# Booster_USER_IFC.net
KiCad netlist of a schematic drawn in Altium Designer
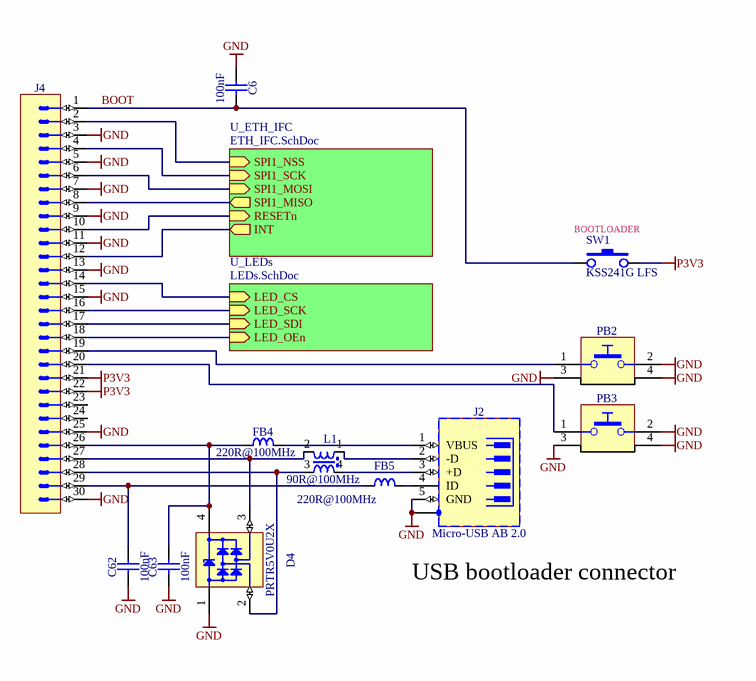
[diagram p0: Booster_USER_IFC.SchDoc]

(export (version "E")
  (design (tool "Eeschema 10.0.6"))
  (components
    (comp (ref "C6")
      (value "100nF")
      (footprint "CAPC1005X55N")
      (description "Non-polarised capacitor")
      (fields
        (field (name "PART NUMBER") "CC0402_100NF_16V_10%_X7R")
        (field (name "VOLTAGE") "16V")
        (field (name "AUTHOR") "CERN DEM JLC")
      )
      (libsource (lib "Capacitors") (part "Capacitor - non polarized"))
    )
    (comp (ref "C62")
      (value "100nF")
      (footprint "CAPC1005X55N")
      (description "Non-polarised capacitor")
      (fields
        (field (name "PART NUMBER") "CC0402_100NF_16V_10%_X7R")
        (field (name "VOLTAGE") "16V")
        (field (name "AUTHOR") "CERN DEM JLC")
      )
      (libsource (lib "Capacitors") (part "Capacitor - non polarized"))
    )
    (comp (ref "C63")
      (value "100nF")
      (footprint "CAPC1005X55N")
      (description "Non-polarised capacitor")
      (fields
        (field (name "PART NUMBER") "CC0402_100NF_16V_10%_X7R")
        (field (name "VOLTAGE") "16V")
        (field (name "AUTHOR") "CERN DEM JLC")
      )
      (libsource (lib "Capacitors") (part "Capacitor - non polarized"))
    )
    (comp (ref "D4")
      (value "PRTR5V0U2X")
      (footprint "SOT190P230X110-4N")
      (description "Ultra Low Capacitance Double Rail-to-Rail ESD Protection Diode")
      (fields
        (field (name "VOLTAGE") "5.5V")
        (field (name "MANUFACTURER") "NXP SEMICONDUCTORS")
        (field (name "AUTHOR") "CERN DEM JLC")
      )
      (libsource (lib "ICs And Semiconductors") (part "PRTR5V0U2X"))
    )
    (comp (ref "FB4")
      (value "220R@100MHz")
      (footprint "INDC2012X105N")
      (description "Inductor")
      (fields
        (field (name "PART NUMBER") "IND0805_MURATA_BLM21PG221SN1D")
        (field (name "POWER") "2A")
        (field (name "AUTHOR") "CERN DEM JLC")
      )
      (libsource (lib "Inductors & Transformers") (part "Inductor"))
    )
    (comp (ref "FB5")
      (value "220R@100MHz")
      (footprint "INDC2012X105N")
      (description "Inductor")
      (fields
        (field (name "PART NUMBER") "IND0805_MURATA_BLM21PG221SN1D")
        (field (name "POWER") "2A")
        (field (name "AUTHOR") "CERN DEM JLC")
      )
      (libsource (lib "Inductors & Transformers") (part "Inductor"))
    )
    (comp (ref "J2")
      (value "Micro-USB AB 2.0")
      (footprint "HIROSE_ZX62RD-AB-5P8")
      (description "5 Pin + 1 Shield USB Receptacle")
      (fields
        (field (name "PART NUMBER") "HIROSE_ZX62RD-AB-5P8")
        (field (name "MANUFACTURER") "HIROSE (HRS)")
        (field (name "AUTHOR") "CERN DEM JLC")
      )
      (libsource (lib "Connectors") (part "Connector USB 5 Pin + 1Shield"))
    )
    (comp (ref "J4")
      (value "~")
      (footprint "3M_N2530-6002RB")
      (description "Connector 30 Male")
      (fields
        (field (name "PART NUMBER") "3M_N2530-6002RB")
        (field (name "MANUFACTURER") "3M")
        (field (name "AUTHOR") "CERN DEM JLC")
      )
      (libsource (lib "Connectors") (part "Connector 30 Male"))
    )
    (comp (ref "L1")
      (value "90R@100MHz")
      (footprint "IND_MURATA_DLW21S")
      (description "Inductor Common Mode")
      (fields
        (field (name "PART NUMBER") "IND_MURATA_DLW21SN900SQ2L")
        (field (name "POWER") "330mA")
        (field (name "AUTHOR") "CERN DEM JLC")
      )
      (libsource (lib "Inductors & Transformers") (part "Inductor Common Mode 1Dot-2 4Dot-3"))
    )
    (comp (ref "PB2")
      (value "Push Button")
      (footprint "PB_TYCO_1-1825027-1")
      (description "Push-Button Switch SPDT")
      (fields
        (field (name "PART NUMBER") "PB_TYCO_1-1825027-1")
        (field (name "MANUFACTURER") "TYCO ELECTRONICS")
        (field (name "AUTHOR") "CERN DEM JLC")
      )
      (libsource (lib "Eletro-mechanical") (part "PB SPST 1NO-2NO 34CASE"))
    )
    (comp (ref "PB3")
      (value "Push Button")
      (footprint "PB_TYCO_1-1825027-1")
      (description "Push-Button Switch SPDT")
      (fields
        (field (name "PART NUMBER") "PB_TYCO_1-1825027-1")
        (field (name "MANUFACTURER") "TYCO ELECTRONICS")
        (field (name "AUTHOR") "CERN DEM JLC")
      )
      (libsource (lib "Eletro-mechanical") (part "PB SPST 1NO-2NO 34CASE"))
    )
    (comp (ref "SW1")
      (value "KSS241G LFS")
      (footprint "KSS241G LFS")
      (description "Push button")
      (libsource (lib "LIBRARY_SCH") (part "SW-TACT_SMD_RA_mini"))
    )
  )
  (nets
    (net (code "1") (name "/BOOT") (class "Default")
      (node (ref "C6") (pin "2") (pinfunction "2_2") (pintype "passive"))
      (node (ref "J4") (pin "1") (pinfunction "1_1") (pintype "bidirectional"))
      (node (ref "SW1") (pin "1") (pinfunction "1_1") (pintype "passive"))
    )
    (net (code "2") (name "/INT") (class "Default")
      (node (ref "J4") (pin "12") (pinfunction "12_12") (pintype "bidirectional"))
    )
    (net (code "3") (name "/LED_CS") (class "Default")
      (node (ref "J4") (pin "14") (pinfunction "14_14") (pintype "bidirectional"))
    )
    (net (code "4") (name "/LED_OEn") (class "Default")
      (node (ref "J4") (pin "18") (pinfunction "18_18") (pintype "bidirectional"))
    )
    (net (code "5") (name "/LED_SCK") (class "Default")
      (node (ref "J4") (pin "16") (pinfunction "16_16") (pintype "bidirectional"))
    )
    (net (code "6") (name "/LED_SDI") (class "Default")
      (node (ref "J4") (pin "17") (pinfunction "17_17") (pintype "bidirectional"))
    )
    (net (code "7") (name "/RESETn") (class "Default")
      (node (ref "J4") (pin "10") (pinfunction "10_10") (pintype "bidirectional"))
    )
    (net (code "8") (name "/SPI1_MISO") (class "Default")
      (node (ref "J4") (pin "8") (pinfunction "8_8") (pintype "bidirectional"))
    )
    (net (code "9") (name "/SPI1_MOSI") (class "Default")
      (node (ref "J4") (pin "6") (pinfunction "6_6") (pintype "bidirectional"))
    )
    (net (code "10") (name "/SPI1_NSS") (class "Default")
      (node (ref "J4") (pin "2") (pinfunction "2_2") (pintype "bidirectional"))
    )
    (net (code "11") (name "/SPI1_SCK") (class "Default")
      (node (ref "J4") (pin "4") (pinfunction "4_4") (pintype "bidirectional"))
    )
    (net (code "12") (name "GND") (class "Default")
      (node (ref "C6") (pin "1") (pinfunction "1_1") (pintype "passive"))
      (node (ref "C62") (pin "1") (pinfunction "1_1") (pintype "passive"))
      (node (ref "C63") (pin "1") (pinfunction "1_1") (pintype "passive"))
      (node (ref "D4") (pin "1") (pinfunction "GND_1") (pintype "power_in"))
      (node (ref "J2") (pin "5") (pinfunction "GND_5") (pintype "bidirectional"))
      (node (ref "J2") (pin "6") (pinfunction "SH_6") (pintype "power_in"))
      (node (ref "J4") (pin "11") (pinfunction "11_11") (pintype "bidirectional"))
      (node (ref "J4") (pin "13") (pinfunction "13_13") (pintype "bidirectional"))
      (node (ref "J4") (pin "15") (pinfunction "15_15") (pintype "bidirectional"))
      (node (ref "J4") (pin "25") (pinfunction "25_25") (pintype "bidirectional"))
      (node (ref "J4") (pin "3") (pinfunction "3_3") (pintype "bidirectional"))
      (node (ref "J4") (pin "30") (pinfunction "30_30") (pintype "bidirectional"))
      (node (ref "J4") (pin "5") (pinfunction "5_5") (pintype "bidirectional"))
      (node (ref "J4") (pin "7") (pinfunction "7_7") (pintype "bidirectional"))
      (node (ref "J4") (pin "9") (pinfunction "9_9") (pintype "bidirectional"))
      (node (ref "PB2") (pin "2") (pinfunction "2_2") (pintype "passive"))
      (node (ref "PB2") (pin "3") (pinfunction "3_3") (pintype "passive"))
      (node (ref "PB2") (pin "4") (pinfunction "4_4") (pintype "passive"))
      (node (ref "PB3") (pin "2") (pinfunction "2_2") (pintype "passive"))
      (node (ref "PB3") (pin "3") (pinfunction "3_3") (pintype "passive"))
      (node (ref "PB3") (pin "4") (pinfunction "4_4") (pintype "passive"))
    )
    (net (code "13") (name "Net-(C62-Pad2)") (class "Default")
      (node (ref "C62") (pin "2") (pinfunction "2_2") (pintype "passive"))
      (node (ref "FB5") (pin "1") (pinfunction "1_1") (pintype "passive"))
      (node (ref "J4") (pin "29") (pinfunction "29_29") (pintype "bidirectional"))
    )
    (net (code "14") (name "Net-(D4-I{slash}O1)") (class "Default")
      (node (ref "D4") (pin "2") (pinfunction "I/O1_2") (pintype "bidirectional"))
      (node (ref "J4") (pin "28") (pinfunction "28_28") (pintype "bidirectional"))
      (node (ref "L1") (pin "3") (pinfunction "3_3") (pintype "passive"))
    )
    (net (code "15") (name "Net-(D4-I{slash}O2)") (class "Default")
      (node (ref "D4") (pin "3") (pinfunction "I/O2_3") (pintype "bidirectional"))
      (node (ref "J4") (pin "27") (pinfunction "27_27") (pintype "bidirectional"))
      (node (ref "L1") (pin "2") (pinfunction "2_2") (pintype "passive"))
    )
    (net (code "16") (name "Net-(D4-VCC)") (class "Default")
      (node (ref "C63") (pin "2") (pinfunction "2_2") (pintype "passive"))
      (node (ref "D4") (pin "4") (pinfunction "VCC_4") (pintype "power_in"))
      (node (ref "FB4") (pin "1") (pinfunction "1_1") (pintype "passive"))
      (node (ref "J4") (pin "26") (pinfunction "26_26") (pintype "bidirectional"))
    )
    (net (code "17") (name "Net-(J2-+D)") (class "Default")
      (node (ref "J2") (pin "3") (pinfunction "+D_3") (pintype "bidirectional"))
      (node (ref "L1") (pin "4") (pinfunction "4_4") (pintype "passive"))
    )
    (net (code "18") (name "Net-(J2--D)") (class "Default")
      (node (ref "J2") (pin "2") (pinfunction "-D_2") (pintype "bidirectional"))
      (node (ref "L1") (pin "1") (pinfunction "1_1") (pintype "passive"))
    )
    (net (code "19") (name "Net-(J2-ID)") (class "Default")
      (node (ref "FB5") (pin "2") (pinfunction "2_2") (pintype "passive"))
      (node (ref "J2") (pin "4") (pinfunction "ID_4") (pintype "passive"))
    )
    (net (code "20") (name "Net-(J2-VBUS)") (class "Default")
      (node (ref "FB4") (pin "2") (pinfunction "2_2") (pintype "passive"))
      (node (ref "J2") (pin "1") (pinfunction "VBUS_1") (pintype "bidirectional"))
    )
    (net (code "21") (name "Net-(J4-Pad19)") (class "Default")
      (node (ref "J4") (pin "19") (pinfunction "19_19") (pintype "bidirectional"))
      (node (ref "PB2") (pin "1") (pinfunction "1_1") (pintype "passive"))
    )
    (net (code "22") (name "Net-(J4-Pad20)") (class "Default")
      (node (ref "J4") (pin "20") (pinfunction "20_20") (pintype "bidirectional"))
      (node (ref "PB3") (pin "1") (pinfunction "1_1") (pintype "passive"))
    )
    (net (code "23") (name "P3V3") (class "Default")
      (node (ref "J4") (pin "21") (pinfunction "21_21") (pintype "bidirectional"))
      (node (ref "J4") (pin "22") (pinfunction "22_22") (pintype "bidirectional"))
      (node (ref "SW1") (pin "2") (pinfunction "2_2") (pintype "passive"))
    )
    (net (code "24") (name "unconnected-(J4-Pad23)") (class "Default")
      (node (ref "J4") (pin "23") (pinfunction "23_23") (pintype "bidirectional"))
    )
    (net (code "25") (name "unconnected-(J4-Pad24)") (class "Default")
      (node (ref "J4") (pin "24") (pinfunction "24_24") (pintype "bidirectional"))
    )
  )
)
